# sht75base.net
KiCad netlist of a schematic drawn in EAGLE
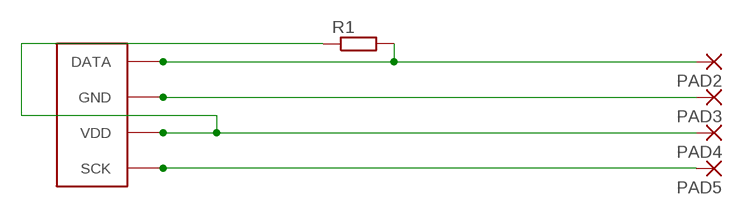
[diagram p0: schematic, sheet 1]

(export (version "E")
  (design (tool "Eeschema 10.0.6"))
  (components
    (comp (ref "PAD2")
      (value "2,54/1,1")
      (footprint "eagle-import:2,54_1,1")
      (libsource (lib "eagle-import") (part "2,54/1,1"))
    )
    (comp (ref "PAD3")
      (value "2,54/1,1")
      (footprint "eagle-import:2,54_1,1")
      (libsource (lib "eagle-import") (part "2,54/1,1"))
    )
    (comp (ref "PAD4")
      (value "2,54/1,1")
      (footprint "eagle-import:2,54_1,1")
      (libsource (lib "eagle-import") (part "2,54/1,1"))
    )
    (comp (ref "PAD5")
      (value "2,54/1,1")
      (footprint "eagle-import:2,54_1,1")
      (libsource (lib "eagle-import") (part "2,54/1,1"))
    )
    (comp (ref "R1")
      (value "R-EU_0309/10")
      (footprint "eagle-import:0309_10")
      (libsource (lib "eagle-import") (part "R-EU_0309/10"))
    )
    (comp (ref "U$2")
      (value "SHT71")
      (footprint "eagle-import:SHT7X")
      (libsource (lib "eagle-import") (part "SHT71"))
    )
  )
  (nets
    (net (code "1") (name "Net-(PAD2-P)") (class "Default")
      (node (ref "PAD2") (pin "1") (pinfunction "P_1") (pintype "passive"))
      (node (ref "R1") (pin "2") (pinfunction "2_2") (pintype "passive"))
      (node (ref "U$2") (pin "4") (pinfunction "DATA_4") (pintype "bidirectional"))
    )
    (net (code "2") (name "Net-(PAD3-P)") (class "Default")
      (node (ref "PAD3") (pin "1") (pinfunction "P_1") (pintype "passive"))
      (node (ref "U$2") (pin "3") (pinfunction "GND_3") (pintype "power_in"))
    )
    (net (code "3") (name "Net-(PAD4-P)") (class "Default")
      (node (ref "PAD4") (pin "1") (pinfunction "P_1") (pintype "passive"))
      (node (ref "R1") (pin "1") (pinfunction "1_1") (pintype "passive"))
      (node (ref "U$2") (pin "2") (pinfunction "VDD_2") (pintype "power_in"))
    )
    (net (code "4") (name "Net-(PAD5-P)") (class "Default")
      (node (ref "PAD5") (pin "1") (pinfunction "P_1") (pintype "passive"))
      (node (ref "U$2") (pin "1") (pinfunction "SCK_1") (pintype "input"))
    )
  )
)
